# SD-CARD_CN.net
KiCad netlist of a schematic drawn in Altium Designer
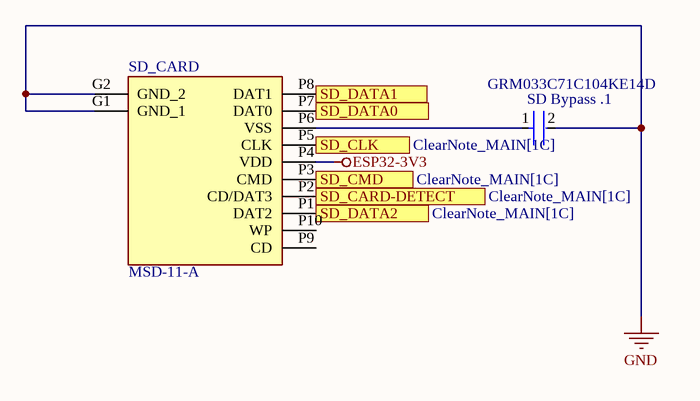
[diagram p0: SD-CARD_CN.SchDoc]

(export (version "E")
  (design (tool "Eeschema 10.0.6"))
  (components
    (comp (ref "SD Bypass .1")
      (value "GRM033C71C104KE14D")
      (footprint "FP-GRM033-0_03-MFG")
      (description "Chip Multilayer Ceramic Capacitors for General Purpose, 0201, 0.10uF, X7S, 22%, 10%, 16V")
      (fields (field (name "TOLERANCE") "10%"))
      (libsource (lib "Altium Content Vault") (part "b4654b650e69147ec39a6b967a45e02"))
    )
    (comp (ref "SD_CARD")
      (value "MSD-11-A")
      (footprint "SamacSys:MSD11A")
      (description "Connector")
      (fields (field (name "MOUSER PART NUMBER") "179-MSD-11-A"))
      (libsource (lib "SamacSys") (part "MSD-11-A"))
    )
  )
  (nets
    (net (code "1") (name "/SD_CARD-DETECT") (class "Default")
      (node (ref "SD_CARD") (pin "P2") (pinfunction "CD/DAT3_P2") (pintype "passive"))
    )
    (net (code "2") (name "/SD_CLK") (class "Default")
      (node (ref "SD_CARD") (pin "P5") (pinfunction "CLK_P5") (pintype "passive"))
    )
    (net (code "3") (name "/SD_CMD") (class "Default")
      (node (ref "SD_CARD") (pin "P3") (pinfunction "CMD_P3") (pintype "passive"))
    )
    (net (code "4") (name "/SD_DATA0") (class "Default")
      (node (ref "SD_CARD") (pin "P7") (pinfunction "DAT0_P7") (pintype "passive"))
    )
    (net (code "5") (name "/SD_DATA1") (class "Default")
      (node (ref "SD_CARD") (pin "P8") (pinfunction "DAT1_P8") (pintype "passive"))
    )
    (net (code "6") (name "/SD_DATA2") (class "Default")
      (node (ref "SD_CARD") (pin "P1") (pinfunction "DAT2_P1") (pintype "passive"))
    )
    (net (code "7") (name "ESP32-3V3") (class "Default")
      (node (ref "SD_CARD") (pin "P4") (pinfunction "VDD_P4") (pintype "passive"))
    )
    (net (code "8") (name "GND") (class "Default")
      (node (ref "SD Bypass .1") (pin "2") (pinfunction "2_2") (pintype "passive"))
      (node (ref "SD_CARD") (pin "G1") (pinfunction "GND_1_G1") (pintype "passive"))
      (node (ref "SD_CARD") (pin "G2") (pinfunction "GND_2_G2") (pintype "passive"))
    )
    (net (code "9") (name "Net-(SD_CARD-VSS)") (class "Default")
      (node (ref "SD Bypass .1") (pin "1") (pinfunction "1_1") (pintype "passive"))
      (node (ref "SD_CARD") (pin "P6") (pinfunction "VSS_P6") (pintype "passive"))
    )
    (net (code "10") (name "unconnected-(SD_CARD-CD-PadP9)") (class "Default")
      (node (ref "SD_CARD") (pin "P9") (pinfunction "CD_P9") (pintype "passive"))
    )
    (net (code "11") (name "unconnected-(SD_CARD-WP-PadP10)") (class "Default")
      (node (ref "SD_CARD") (pin "P10") (pinfunction "WP_P10") (pintype "passive"))
    )
  )
)
